# 2_FPGA.net
KiCad netlist of a schematic drawn in Altium Designer
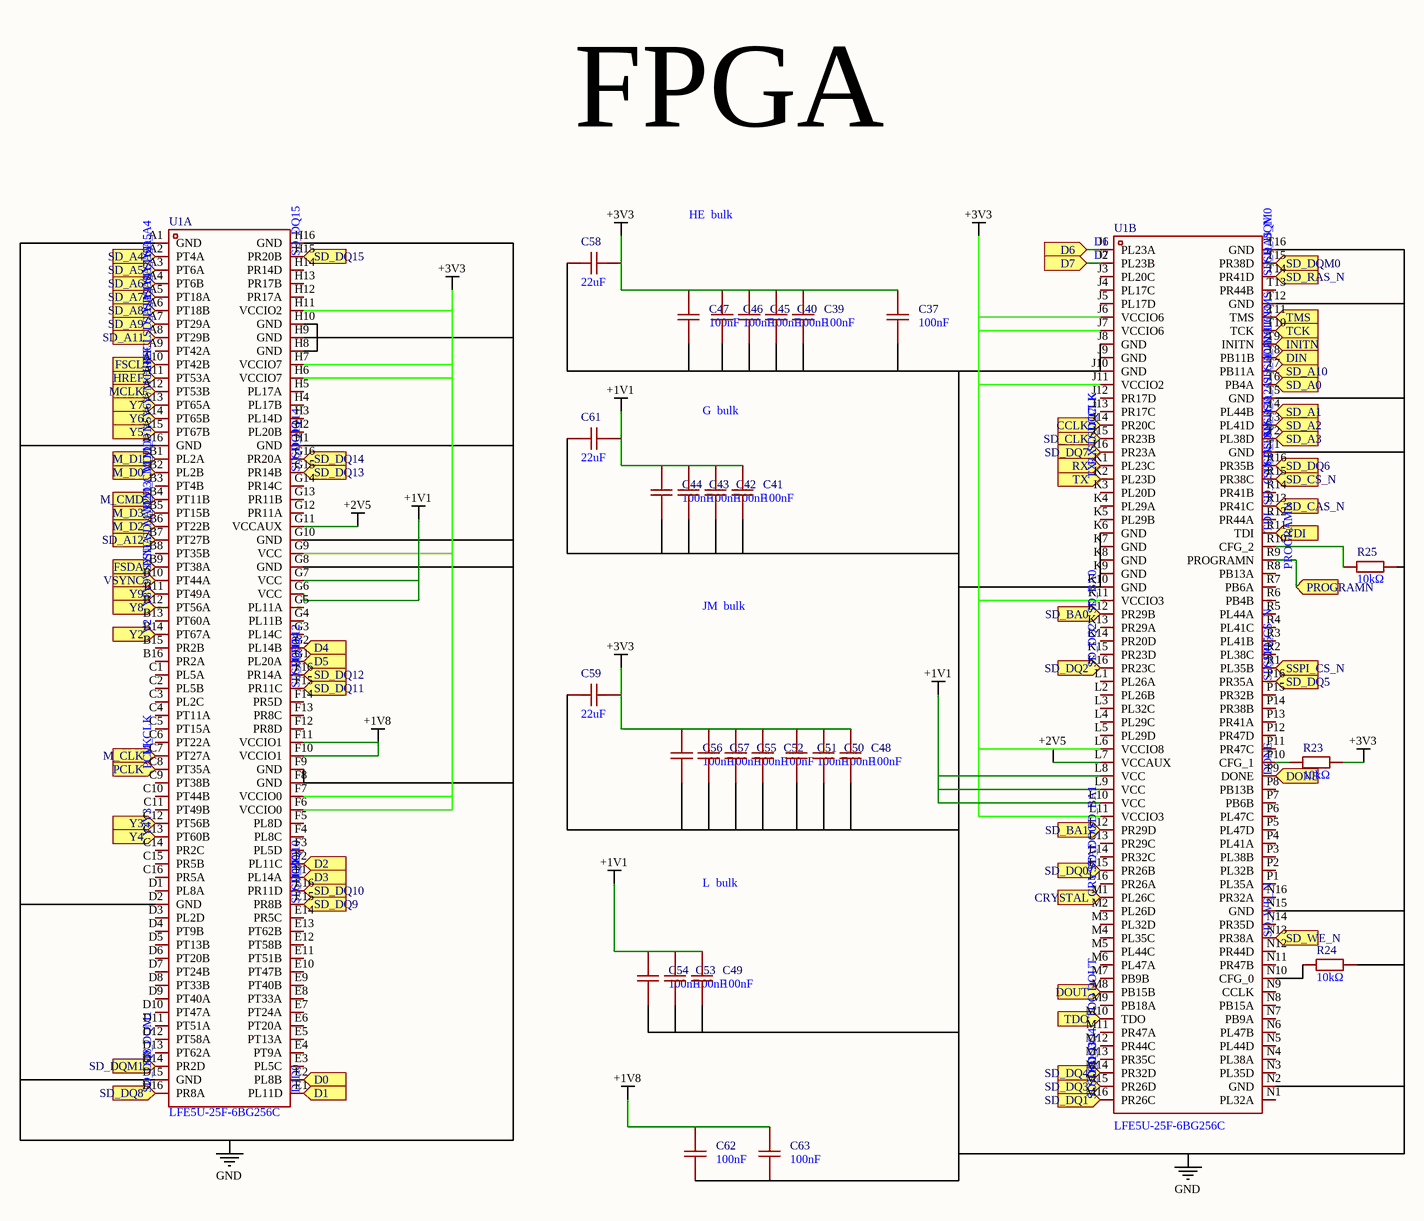
[diagram p0: 2_FPGA.schdoc]

(export (version "E")
  (design (tool "Eeschema 10.0.6"))
  (components
    (comp (ref "C37")
      (value "100nF")
      (footprint "C01005")
      (fields
        (field (name "MANUFACTURER") "muRata(村田)")
        (field (name "MANUFACTURER PART") "GRM022R60J104KE15D")
        (field (name "TOLERANCE") "±10%")
      )
      (libsource (lib "altium-import") (part "root_2_GRM022R60J104KE15D_"))
    )
    (comp (ref "C39")
      (value "100nF")
      (footprint "C01005")
      (fields
        (field (name "MANUFACTURER") "muRata(村田)")
        (field (name "MANUFACTURER PART") "GRM022R60J104KE15D")
        (field (name "TOLERANCE") "±10%")
      )
      (libsource (lib "altium-import") (part "root_2_GRM022R60J104KE15D_"))
    )
    (comp (ref "C40")
      (value "100nF")
      (footprint "C01005")
      (fields
        (field (name "MANUFACTURER") "muRata(村田)")
        (field (name "MANUFACTURER PART") "GRM022R60J104KE15D")
        (field (name "TOLERANCE") "±10%")
      )
      (libsource (lib "altium-import") (part "root_2_GRM022R60J104KE15D_"))
    )
    (comp (ref "C41")
      (value "100nF")
      (footprint "C01005")
      (fields
        (field (name "MANUFACTURER") "muRata(村田)")
        (field (name "MANUFACTURER PART") "GRM022R60J104KE15D")
        (field (name "TOLERANCE") "±10%")
      )
      (libsource (lib "altium-import") (part "root_2_GRM022R60J104KE15D_"))
    )
    (comp (ref "C42")
      (value "100nF")
      (footprint "C01005")
      (fields
        (field (name "MANUFACTURER") "muRata(村田)")
        (field (name "MANUFACTURER PART") "GRM022R60J104KE15D")
        (field (name "TOLERANCE") "±10%")
      )
      (libsource (lib "altium-import") (part "root_2_GRM022R60J104KE15D_"))
    )
    (comp (ref "C43")
      (value "100nF")
      (footprint "C01005")
      (fields
        (field (name "MANUFACTURER") "muRata(村田)")
        (field (name "MANUFACTURER PART") "GRM022R60J104KE15D")
        (field (name "TOLERANCE") "±10%")
      )
      (libsource (lib "altium-import") (part "root_2_GRM022R60J104KE15D_"))
    )
    (comp (ref "C44")
      (value "100nF")
      (footprint "C01005")
      (fields
        (field (name "MANUFACTURER") "muRata(村田)")
        (field (name "MANUFACTURER PART") "GRM022R60J104KE15D")
        (field (name "TOLERANCE") "±10%")
      )
      (libsource (lib "altium-import") (part "root_2_GRM022R60J104KE15D_"))
    )
    (comp (ref "C45")
      (value "100nF")
      (footprint "C01005")
      (fields
        (field (name "MANUFACTURER") "muRata(村田)")
        (field (name "MANUFACTURER PART") "GRM022R60J104KE15D")
        (field (name "TOLERANCE") "±10%")
      )
      (libsource (lib "altium-import") (part "root_2_GRM022R60J104KE15D_"))
    )
    (comp (ref "C46")
      (value "100nF")
      (footprint "C01005")
      (fields
        (field (name "MANUFACTURER") "muRata(村田)")
        (field (name "MANUFACTURER PART") "GRM022R60J104KE15D")
        (field (name "TOLERANCE") "±10%")
      )
      (libsource (lib "altium-import") (part "root_2_GRM022R60J104KE15D_"))
    )
    (comp (ref "C47")
      (value "100nF")
      (footprint "C01005")
      (fields
        (field (name "MANUFACTURER") "muRata(村田)")
        (field (name "MANUFACTURER PART") "GRM022R60J104KE15D")
        (field (name "TOLERANCE") "±10%")
      )
      (libsource (lib "altium-import") (part "root_2_GRM022R60J104KE15D_"))
    )
    (comp (ref "C48")
      (value "100nF")
      (footprint "C01005")
      (fields
        (field (name "MANUFACTURER") "muRata(村田)")
        (field (name "MANUFACTURER PART") "GRM022R60J104KE15D")
        (field (name "TOLERANCE") "±10%")
      )
      (libsource (lib "altium-import") (part "root_2_GRM022R60J104KE15D_"))
    )
    (comp (ref "C49")
      (value "100nF")
      (footprint "C01005")
      (fields
        (field (name "MANUFACTURER") "muRata(村田)")
        (field (name "MANUFACTURER PART") "GRM022R60J104KE15D")
        (field (name "TOLERANCE") "±10%")
      )
      (libsource (lib "altium-import") (part "root_2_GRM022R60J104KE15D_"))
    )
    (comp (ref "C50")
      (value "100nF")
      (footprint "C01005")
      (fields
        (field (name "MANUFACTURER") "muRata(村田)")
        (field (name "MANUFACTURER PART") "GRM022R60J104KE15D")
        (field (name "TOLERANCE") "±10%")
      )
      (libsource (lib "altium-import") (part "root_2_GRM022R60J104KE15D_"))
    )
    (comp (ref "C51")
      (value "100nF")
      (footprint "C01005")
      (fields
        (field (name "MANUFACTURER") "muRata(村田)")
        (field (name "MANUFACTURER PART") "GRM022R60J104KE15D")
        (field (name "TOLERANCE") "±10%")
      )
      (libsource (lib "altium-import") (part "root_2_GRM022R60J104KE15D_"))
    )
    (comp (ref "C52")
      (value "100nF")
      (footprint "C01005")
      (fields
        (field (name "MANUFACTURER") "muRata(村田)")
        (field (name "MANUFACTURER PART") "GRM022R60J104KE15D")
        (field (name "TOLERANCE") "±10%")
      )
      (libsource (lib "altium-import") (part "root_2_GRM022R60J104KE15D_"))
    )
    (comp (ref "C53")
      (value "100nF")
      (footprint "C01005")
      (fields
        (field (name "MANUFACTURER") "muRata(村田)")
        (field (name "MANUFACTURER PART") "GRM022R60J104KE15D")
        (field (name "TOLERANCE") "±10%")
      )
      (libsource (lib "altium-import") (part "root_2_GRM022R60J104KE15D_"))
    )
    (comp (ref "C54")
      (value "100nF")
      (footprint "C01005")
      (fields
        (field (name "MANUFACTURER") "muRata(村田)")
        (field (name "MANUFACTURER PART") "GRM022R60J104KE15D")
        (field (name "TOLERANCE") "±10%")
      )
      (libsource (lib "altium-import") (part "root_2_GRM022R60J104KE15D_"))
    )
    (comp (ref "C55")
      (value "100nF")
      (footprint "C01005")
      (fields
        (field (name "MANUFACTURER") "muRata(村田)")
        (field (name "MANUFACTURER PART") "GRM022R60J104KE15D")
        (field (name "TOLERANCE") "±10%")
      )
      (libsource (lib "altium-import") (part "root_2_GRM022R60J104KE15D_"))
    )
    (comp (ref "C56")
      (value "100nF")
      (footprint "C01005")
      (fields
        (field (name "MANUFACTURER") "muRata(村田)")
        (field (name "MANUFACTURER PART") "GRM022R60J104KE15D")
        (field (name "TOLERANCE") "±10%")
      )
      (libsource (lib "altium-import") (part "root_2_GRM022R60J104KE15D_"))
    )
    (comp (ref "C57")
      (value "100nF")
      (footprint "C01005")
      (fields
        (field (name "MANUFACTURER") "muRata(村田)")
        (field (name "MANUFACTURER PART") "GRM022R60J104KE15D")
        (field (name "TOLERANCE") "±10%")
      )
      (libsource (lib "altium-import") (part "root_2_GRM022R60J104KE15D_"))
    )
    (comp (ref "C58")
      (value "22uF")
      (footprint "C0603")
      (fields
        (field (name "MANUFACTURER") "CCTC(三环)")
        (field (name "MANUFACTURER PART") "TCC0603X5R226M6R3CT")
        (field (name "TOLERANCE") "±20%")
      )
      (libsource (lib "altium-import") (part "root_1_TCC0603X5R226M6R3CT_"))
    )
    (comp (ref "C59")
      (value "22uF")
      (footprint "C0603")
      (fields
        (field (name "MANUFACTURER") "CCTC(三环)")
        (field (name "MANUFACTURER PART") "TCC0603X5R226M6R3CT")
        (field (name "TOLERANCE") "±20%")
      )
      (libsource (lib "altium-import") (part "root_1_TCC0603X5R226M6R3CT_"))
    )
    (comp (ref "C61")
      (value "22uF")
      (footprint "C0603")
      (fields
        (field (name "MANUFACTURER") "CCTC(三环)")
        (field (name "MANUFACTURER PART") "TCC0603X5R226M6R3CT")
        (field (name "TOLERANCE") "±20%")
      )
      (libsource (lib "altium-import") (part "root_1_TCC0603X5R226M6R3CT_"))
    )
    (comp (ref "C62")
      (value "100nF")
      (footprint "C01005")
      (fields
        (field (name "MANUFACTURER") "muRata(村田)")
        (field (name "MANUFACTURER PART") "GRM022R60J104KE15D")
        (field (name "TOLERANCE") "±10%")
      )
      (libsource (lib "altium-import") (part "root_2_GRM022R60J104KE15D_"))
    )
    (comp (ref "C63")
      (value "100nF")
      (footprint "C01005")
      (fields
        (field (name "MANUFACTURER") "muRata(村田)")
        (field (name "MANUFACTURER PART") "GRM022R60J104KE15D")
        (field (name "TOLERANCE") "±10%")
      )
      (libsource (lib "altium-import") (part "root_2_GRM022R60J104KE15D_"))
    )
    (comp (ref "R23")
      (value "10kΩ")
      (footprint "R0402")
      (fields
        (field (name "MANUFACTURER") "UNI-ROYAL(厚声)")
        (field (name "MANUFACTURER PART") "0402WGF1002TCE")
        (field (name "TOLERANCE") "±1%")
      )
      (libsource (lib "altium-import") (part "root_2_0402WGF1002TCE_"))
    )
    (comp (ref "R24")
      (value "10kΩ")
      (footprint "R0402")
      (fields
        (field (name "MANUFACTURER") "UNI-ROYAL(厚声)")
        (field (name "MANUFACTURER PART") "0402WGF1002TCE")
        (field (name "TOLERANCE") "±1%")
      )
      (libsource (lib "altium-import") (part "root_2_0402WGF1002TCE_"))
    )
    (comp (ref "R25")
      (value "10kΩ")
      (footprint "R0402")
      (fields
        (field (name "MANUFACTURER") "UNI-ROYAL(厚声)")
        (field (name "MANUFACTURER PART") "0402WGF1002TCE")
        (field (name "TOLERANCE") "±1%")
      )
      (libsource (lib "altium-import") (part "root_2_0402WGF1002TCE_"))
    )
    (comp (ref "U1")
      (value "LFE5U-25F-6BG256C")
      (footprint "CABGA-256_L14.0-W14.0-R16-C16-P0.80-TL")
      (fields (field (name "MANUFACTURER") "LATTICE(莱迪思)"))
      (libsource (lib "altium-import") (part "root_0_LFE5U-25F-6BG256C_"))
    )
  )
  (nets
    (net (code "1") (name "+1V1") (class "Default")
      (node (ref "C41") (pin "1") (pinfunction "1_1") (pintype "passive"))
      (node (ref "C42") (pin "1") (pinfunction "1_1") (pintype "passive"))
      (node (ref "C43") (pin "1") (pinfunction "1_1") (pintype "passive"))
      (node (ref "C44") (pin "1") (pinfunction "1_1") (pintype "passive"))
      (node (ref "C49") (pin "1") (pinfunction "1_1") (pintype "passive"))
      (node (ref "C53") (pin "1") (pinfunction "1_1") (pintype "passive"))
      (node (ref "C54") (pin "1") (pinfunction "1_1") (pintype "passive"))
      (node (ref "C61") (pin "1") (pinfunction "1_1") (pintype "passive"))
      (node (ref "U1") (pin "G6") (pinfunction "VCC_G6") (pintype "passive"))
      (node (ref "U1") (pin "G7") (pinfunction "VCC_G7") (pintype "passive"))
      (node (ref "U1") (pin "L10") (pinfunction "VCC_L10") (pintype "passive"))
      (node (ref "U1") (pin "L8") (pinfunction "VCC_L8") (pintype "passive"))
      (node (ref "U1") (pin "L9") (pinfunction "VCC_L9") (pintype "passive"))
    )
    (net (code "2") (name "+1V8") (class "Default")
      (node (ref "C62") (pin "1") (pinfunction "1_1") (pintype "passive"))
      (node (ref "C63") (pin "1") (pinfunction "1_1") (pintype "passive"))
      (node (ref "U1") (pin "F10") (pinfunction "VCCIO1_F10") (pintype "passive"))
      (node (ref "U1") (pin "F11") (pinfunction "VCCIO1_F11") (pintype "passive"))
    )
    (net (code "3") (name "+2V5") (class "Default")
      (node (ref "U1") (pin "G11") (pinfunction "VCCAUX_G11") (pintype "passive"))
      (node (ref "U1") (pin "L7") (pinfunction "VCCAUX_L7") (pintype "passive"))
    )
    (net (code "4") (name "+3V3") (class "Default")
      (node (ref "C37") (pin "1") (pinfunction "1_1") (pintype "passive"))
      (node (ref "C39") (pin "1") (pinfunction "1_1") (pintype "passive"))
      (node (ref "C40") (pin "1") (pinfunction "1_1") (pintype "passive"))
      (node (ref "C45") (pin "1") (pinfunction "1_1") (pintype "passive"))
      (node (ref "C46") (pin "1") (pinfunction "1_1") (pintype "passive"))
      (node (ref "C47") (pin "1") (pinfunction "1_1") (pintype "passive"))
      (node (ref "C48") (pin "1") (pinfunction "1_1") (pintype "passive"))
      (node (ref "C50") (pin "1") (pinfunction "1_1") (pintype "passive"))
      (node (ref "C51") (pin "1") (pinfunction "1_1") (pintype "passive"))
      (node (ref "C52") (pin "1") (pinfunction "1_1") (pintype "passive"))
      (node (ref "C55") (pin "1") (pinfunction "1_1") (pintype "passive"))
      (node (ref "C56") (pin "1") (pinfunction "1_1") (pintype "passive"))
      (node (ref "C57") (pin "1") (pinfunction "1_1") (pintype "passive"))
      (node (ref "C58") (pin "1") (pinfunction "1_1") (pintype "passive"))
      (node (ref "C59") (pin "1") (pinfunction "1_1") (pintype "passive"))
      (node (ref "R23") (pin "1") (pinfunction "1_1") (pintype "passive"))
      (node (ref "U1") (pin "F6") (pinfunction "VCCIO0_F6") (pintype "passive"))
      (node (ref "U1") (pin "F7") (pinfunction "VCCIO0_F7") (pintype "passive"))
      (node (ref "U1") (pin "G9") (pinfunction "VCC_G9") (pintype "passive"))
      (node (ref "U1") (pin "H11") (pinfunction "VCCIO2_H11") (pintype "passive"))
      (node (ref "U1") (pin "H6") (pinfunction "VCCIO7_H6") (pintype "passive"))
      (node (ref "U1") (pin "H7") (pinfunction "VCCIO7_H7") (pintype "passive"))
      (node (ref "U1") (pin "J11") (pinfunction "VCCIO2_J11") (pintype "passive"))
      (node (ref "U1") (pin "J6") (pinfunction "VCCIO6_J6") (pintype "passive"))
      (node (ref "U1") (pin "J7") (pinfunction "VCCIO6_J7") (pintype "passive"))
      (node (ref "U1") (pin "K11") (pinfunction "VCCIO3_K11") (pintype "passive"))
      (node (ref "U1") (pin "L11") (pinfunction "VCCIO3_L11") (pintype "passive"))
      (node (ref "U1") (pin "L6") (pinfunction "VCCIO8_L6") (pintype "passive"))
    )
    (net (code "5") (name "/CCLK") (class "Default")
      (node (ref "U1") (pin "J14") (pinfunction "PR20C_J14") (pintype "passive"))
    )
    (net (code "6") (name "/CRYSTAL") (class "Default")
      (node (ref "U1") (pin "M1") (pinfunction "PL26C_M1") (pintype "passive"))
    )
    (net (code "7") (name "/D0") (class "Default")
      (node (ref "U1") (pin "E2") (pinfunction "PL8B_E2") (pintype "passive"))
    )
    (net (code "8") (name "/D1") (class "Default")
      (node (ref "U1") (pin "E1") (pinfunction "PL11D_E1") (pintype "passive"))
    )
    (net (code "9") (name "/D2") (class "Default")
      (node (ref "U1") (pin "F2") (pinfunction "PL11C_F2") (pintype "passive"))
    )
    (net (code "10") (name "/D3") (class "Default")
      (node (ref "U1") (pin "F1") (pinfunction "PL14A_F1") (pintype "passive"))
    )
    (net (code "11") (name "/D4") (class "Default")
      (node (ref "U1") (pin "G2") (pinfunction "PL14B_G2") (pintype "passive"))
    )
    (net (code "12") (name "/D5") (class "Default")
      (node (ref "U1") (pin "G1") (pinfunction "PL20A_G1") (pintype "passive"))
    )
    (net (code "13") (name "/D6") (class "Default")
      (node (ref "U1") (pin "J1") (pinfunction "PL23A_J1") (pintype "passive"))
    )
    (net (code "14") (name "/D7") (class "Default")
      (node (ref "U1") (pin "J2") (pinfunction "PL23B_J2") (pintype "passive"))
    )
    (net (code "15") (name "/DIN") (class "Default")
      (node (ref "U1") (pin "T8") (pinfunction "PB11B_T8") (pintype "passive"))
    )
    (net (code "16") (name "/DONE") (class "Default")
      (node (ref "U1") (pin "P9") (pinfunction "DONE_P9") (pintype "passive"))
    )
    (net (code "17") (name "/DOUT") (class "Default")
      (node (ref "U1") (pin "M8") (pinfunction "PB15B_M8") (pintype "passive"))
    )
    (net (code "18") (name "/FSCL") (class "Default")
      (node (ref "U1") (pin "A10") (pinfunction "PT42B_A10") (pintype "passive"))
    )
    (net (code "19") (name "/FSDA") (class "Default")
      (node (ref "U1") (pin "B9") (pinfunction "PT38A_B9") (pintype "passive"))
    )
    (net (code "20") (name "/HREF") (class "Default")
      (node (ref "U1") (pin "A11") (pinfunction "PT53A_A11") (pintype "passive"))
    )
    (net (code "21") (name "/INITN") (class "Default")
      (node (ref "U1") (pin "T9") (pinfunction "INITN_T9") (pintype "passive"))
    )
    (net (code "22") (name "/MCLK") (class "Default")
      (node (ref "U1") (pin "A12") (pinfunction "PT53B_A12") (pintype "passive"))
    )
    (net (code "23") (name "/M_CLK") (class "Default")
      (node (ref "U1") (pin "C7") (pinfunction "PT27A_C7") (pintype "passive"))
    )
    (net (code "24") (name "/M_CMD") (class "Default")
      (node (ref "U1") (pin "B4") (pinfunction "PT11B_B4") (pintype "passive"))
    )
    (net (code "25") (name "/M_D0") (class "Default")
      (node (ref "U1") (pin "B2") (pinfunction "PL2B_B2") (pintype "passive"))
    )
    (net (code "26") (name "/M_D1") (class "Default")
      (node (ref "U1") (pin "B1") (pinfunction "PL2A_B1") (pintype "passive"))
    )
    (net (code "27") (name "/M_D2") (class "Default")
      (node (ref "U1") (pin "B6") (pinfunction "PT22B_B6") (pintype "passive"))
    )
    (net (code "28") (name "/M_D3") (class "Default")
      (node (ref "U1") (pin "B5") (pinfunction "PT15B_B5") (pintype "passive"))
    )
    (net (code "29") (name "/PCLK") (class "Default")
      (node (ref "U1") (pin "C8") (pinfunction "PT35A_C8") (pintype "passive"))
    )
    (net (code "30") (name "/PROGRAMN") (class "Default")
      (node (ref "U1") (pin "R9") (pinfunction "PROGRAMN_R9") (pintype "passive"))
    )
    (net (code "31") (name "/RX") (class "Default")
      (node (ref "U1") (pin "K1") (pinfunction "PL23C_K1") (pintype "passive"))
    )
    (net (code "32") (name "/SD_A0") (class "Default")
      (node (ref "U1") (pin "T6") (pinfunction "PB4A_T6") (pintype "passive"))
    )
    (net (code "33") (name "/SD_A1") (class "Default")
      (node (ref "U1") (pin "T4") (pinfunction "PL44B_T4") (pintype "passive"))
    )
    (net (code "34") (name "/SD_A2") (class "Default")
      (node (ref "U1") (pin "T3") (pinfunction "PL41D_T3") (pintype "passive"))
    )
    (net (code "35") (name "/SD_A3") (class "Default")
      (node (ref "U1") (pin "T2") (pinfunction "PL38D_T2") (pintype "passive"))
    )
    (net (code "36") (name "/SD_A4") (class "Default")
      (node (ref "U1") (pin "A2") (pinfunction "PT4A_A2") (pintype "passive"))
    )
    (net (code "37") (name "/SD_A5") (class "Default")
      (node (ref "U1") (pin "A3") (pinfunction "PT6A_A3") (pintype "passive"))
    )
    (net (code "38") (name "/SD_A6") (class "Default")
      (node (ref "U1") (pin "A4") (pinfunction "PT6B_A4") (pintype "passive"))
    )
    (net (code "39") (name "/SD_A7") (class "Default")
      (node (ref "U1") (pin "A5") (pinfunction "PT18A_A5") (pintype "passive"))
    )
    (net (code "40") (name "/SD_A8") (class "Default")
      (node (ref "U1") (pin "A6") (pinfunction "PT18B_A6") (pintype "passive"))
    )
    (net (code "41") (name "/SD_A9") (class "Default")
      (node (ref "U1") (pin "A7") (pinfunction "PT29A_A7") (pintype "passive"))
    )
    (net (code "42") (name "/SD_A10") (class "Default")
      (node (ref "U1") (pin "T7") (pinfunction "PB11A_T7") (pintype "passive"))
    )
    (net (code "43") (name "/SD_A11") (class "Default")
      (node (ref "U1") (pin "A8") (pinfunction "PT29B_A8") (pintype "passive"))
    )
    (net (code "44") (name "/SD_A12") (class "Default")
      (node (ref "U1") (pin "B7") (pinfunction "PT27B_B7") (pintype "passive"))
    )
    (net (code "45") (name "/SD_BA0") (class "Default")
      (node (ref "U1") (pin "K12") (pinfunction "PR29B_K12") (pintype "passive"))
    )
    (net (code "46") (name "/SD_BA1") (class "Default")
      (node (ref "U1") (pin "L12") (pinfunction "PR29D_L12") (pintype "passive"))
    )
    (net (code "47") (name "/SD_CAS_N") (class "Default")
      (node (ref "U1") (pin "R13") (pinfunction "PR41C_R13") (pintype "passive"))
    )
    (net (code "48") (name "/SD_CLK") (class "Default")
      (node (ref "U1") (pin "J15") (pinfunction "PR23B_J15") (pintype "passive"))
    )
    (net (code "49") (name "/SD_CS_N") (class "Default")
      (node (ref "U1") (pin "R15") (pinfunction "PR38C_R15") (pintype "passive"))
    )
    (net (code "50") (name "/SD_DQ0") (class "Default")
      (node (ref "U1") (pin "L15") (pinfunction "PR26B_L15") (pintype "passive"))
    )
    (net (code "51") (name "/SD_DQ1") (class "Default")
      (node (ref "U1") (pin "M16") (pinfunction "PR26C_M16") (pintype "passive"))
    )
    (net (code "52") (name "/SD_DQ2") (class "Default")
      (node (ref "U1") (pin "K16") (pinfunction "PR23C_K16") (pintype "passive"))
    )
    (net (code "53") (name "/SD_DQ3") (class "Default")
      (node (ref "U1") (pin "M15") (pinfunction "PR26D_M15") (pintype "passive"))
    )
    (net (code "54") (name "/SD_DQ4") (class "Default")
      (node (ref "U1") (pin "M14") (pinfunction "PR32D_M14") (pintype "passive"))
    )
    (net (code "55") (name "/SD_DQ5") (class "Default")
      (node (ref "U1") (pin "P16") (pinfunction "PR35A_P16") (pintype "passive"))
    )
    (net (code "56") (name "/SD_DQ6") (class "Default")
      (node (ref "U1") (pin "R16") (pinfunction "PR35B_R16") (pintype "passive"))
    )
    (net (code "57") (name "/SD_DQ7") (class "Default")
      (node (ref "U1") (pin "J16") (pinfunction "PR23A_J16") (pintype "passive"))
    )
    (net (code "58") (name "/SD_DQ8") (class "Default")
      (node (ref "U1") (pin "D16") (pinfunction "PR8A_D16") (pintype "passive"))
    )
    (net (code "59") (name "/SD_DQ9") (class "Default")
      (node (ref "U1") (pin "E15") (pinfunction "PR8B_E15") (pintype "passive"))
    )
    (net (code "60") (name "/SD_DQ10") (class "Default")
      (node (ref "U1") (pin "E16") (pinfunction "PR11D_E16") (pintype "passive"))
    )
    (net (code "61") (name "/SD_DQ11") (class "Default")
      (node (ref "U1") (pin "F15") (pinfunction "PR11C_F15") (pintype "passive"))
    )
    (net (code "62") (name "/SD_DQ12") (class "Default")
      (node (ref "U1") (pin "F16") (pinfunction "PR14A_F16") (pintype "passive"))
    )
    (net (code "63") (name "/SD_DQ13") (class "Default")
      (node (ref "U1") (pin "G15") (pinfunction "PR14B_G15") (pintype "passive"))
    )
    (net (code "64") (name "/SD_DQ14") (class "Default")
      (node (ref "U1") (pin "G16") (pinfunction "PR20A_G16") (pintype "passive"))
    )
    (net (code "65") (name "/SD_DQ15") (class "Default")
      (node (ref "U1") (pin "H15") (pinfunction "PR20B_H15") (pintype "passive"))
    )
    (net (code "66") (name "/SD_DQM0") (class "Default")
      (node (ref "U1") (pin "T15") (pinfunction "PR38D_T15") (pintype "passive"))
    )
    (net (code "67") (name "/SD_DQM1") (class "Default")
      (node (ref "U1") (pin "D14") (pinfunction "PR2D_D14") (pintype "passive"))
    )
    (net (code "68") (name "/SD_RAS_N") (class "Default")
      (node (ref "U1") (pin "T14") (pinfunction "PR41D_T14") (pintype "passive"))
    )
    (net (code "69") (name "/SD_WE_N") (class "Default")
      (node (ref "U1") (pin "N13") (pinfunction "PR38A_N13") (pintype "passive"))
    )
    (net (code "70") (name "/SSPI_CS_N") (class "Default")
      (node (ref "U1") (pin "R1") (pinfunction "PL35B_R1") (pintype "passive"))
    )
    (net (code "71") (name "/TCK") (class "Default")
      (node (ref "U1") (pin "T10") (pinfunction "TCK_T10") (pintype "passive"))
    )
    (net (code "72") (name "/TDI") (class "Default")
      (node (ref "U1") (pin "R11") (pinfunction "TDI_R11") (pintype "passive"))
    )
    (net (code "73") (name "/TDO") (class "Default")
      (node (ref "U1") (pin "M10") (pinfunction "TDO_M10") (pintype "passive"))
    )
    (net (code "74") (name "/TMS") (class "Default")
      (node (ref "U1") (pin "T11") (pinfunction "TMS_T11") (pintype "passive"))
    )
    (net (code "75") (name "/TX") (class "Default")
      (node (ref "U1") (pin "K2") (pinfunction "PL23D_K2") (pintype "passive"))
    )
    (net (code "76") (name "/VSYNC") (class "Default")
      (node (ref "U1") (pin "B10") (pinfunction "PT44A_B10") (pintype "passive"))
    )
    (net (code "77") (name "/Y2") (class "Default")
      (node (ref "U1") (pin "B14") (pinfunction "PT67A_B14") (pintype "passive"))
    )
    (net (code "78") (name "/Y3") (class "Default")
      (node (ref "U1") (pin "C12") (pinfunction "PT56B_C12") (pintype "passive"))
    )
    (net (code "79") (name "/Y4") (class "Default")
      (node (ref "U1") (pin "C13") (pinfunction "PT60B_C13") (pintype "passive"))
    )
    (net (code "80") (name "/Y5") (class "Default")
      (node (ref "U1") (pin "A15") (pinfunction "PT67B_A15") (pintype "passive"))
    )
    (net (code "81") (name "/Y6") (class "Default")
      (node (ref "U1") (pin "A14") (pinfunction "PT65B_A14") (pintype "passive"))
    )
    (net (code "82") (name "/Y7") (class "Default")
      (node (ref "U1") (pin "A13") (pinfunction "PT65A_A13") (pintype "passive"))
    )
    (net (code "83") (name "/Y8") (class "Default")
      (node (ref "U1") (pin "B12") (pinfunction "PT56A_B12") (pintype "passive"))
    )
    (net (code "84") (name "/Y9") (class "Default")
      (node (ref "U1") (pin "B11") (pinfunction "PT49A_B11") (pintype "passive"))
    )
    (net (code "85") (name "GND") (class "Default")
      (node (ref "C37") (pin "2") (pinfunction "2_2") (pintype "passive"))
      (node (ref "C39") (pin "2") (pinfunction "2_2") (pintype "passive"))
      (node (ref "C40") (pin "2") (pinfunction "2_2") (pintype "passive"))
      (node (ref "C41") (pin "2") (pinfunction "2_2") (pintype "passive"))
      (node (ref "C42") (pin "2") (pinfunction "2_2") (pintype "passive"))
      (node (ref "C43") (pin "2") (pinfunction "2_2") (pintype "passive"))
      (node (ref "C44") (pin "2") (pinfunction "2_2") (pintype "passive"))
      (node (ref "C45") (pin "2") (pinfunction "2_2") (pintype "passive"))
      (node (ref "C46") (pin "2") (pinfunction "2_2") (pintype "passive"))
      (node (ref "C47") (pin "2") (pinfunction "2_2") (pintype "passive"))
      (node (ref "C48") (pin "2") (pinfunction "2_2") (pintype "passive"))
      (node (ref "C49") (pin "2") (pinfunction "2_2") (pintype "passive"))
      (node (ref "C50") (pin "2") (pinfunction "2_2") (pintype "passive"))
      (node (ref "C51") (pin "2") (pinfunction "2_2") (pintype "passive"))
      (node (ref "C52") (pin "2") (pinfunction "2_2") (pintype "passive"))
      (node (ref "C53") (pin "2") (pinfunction "2_2") (pintype "passive"))
      (node (ref "C54") (pin "2") (pinfunction "2_2") (pintype "passive"))
      (node (ref "C55") (pin "2") (pinfunction "2_2") (pintype "passive"))
      (node (ref "C56") (pin "2") (pinfunction "2_2") (pintype "passive"))
      (node (ref "C57") (pin "2") (pinfunction "2_2") (pintype "passive"))
      (node (ref "C58") (pin "2") (pinfunction "2_2") (pintype "passive"))
      (node (ref "C59") (pin "2") (pinfunction "2_2") (pintype "passive"))
      (node (ref "C61") (pin "2") (pinfunction "2_2") (pintype "passive"))
      (node (ref "C62") (pin "2") (pinfunction "2_2") (pintype "passive"))
      (node (ref "C63") (pin "2") (pinfunction "2_2") (pintype "passive"))
      (node (ref "R24") (pin "1") (pinfunction "1_1") (pintype "passive"))
      (node (ref "R25") (pin "1") (pinfunction "1_1") (pintype "passive"))
      (node (ref "U1") (pin "A1") (pinfunction "GND_A1") (pintype "passive"))
      (node (ref "U1") (pin "A16") (pinfunction "GND_A16") (pintype "passive"))
      (node (ref "U1") (pin "D15") (pinfunction "GND_D15") (pintype "passive"))
      (node (ref "U1") (pin "D2") (pinfunction "GND_D2") (pintype "passive"))
      (node (ref "U1") (pin "F8") (pinfunction "GND_F8") (pintype "passive"))
      (node (ref "U1") (pin "F9") (pinfunction "GND_F9") (pintype "passive"))
      (node (ref "U1") (pin "G10") (pinfunction "GND_G10") (pintype "passive"))
      (node (ref "U1") (pin "G8") (pinfunction "GND_G8") (pintype "passive"))
      (node (ref "U1") (pin "H1") (pinfunction "GND_H1") (pintype "passive"))
      (node (ref "U1") (pin "H10") (pinfunction "GND_H10") (pintype "passive"))
      (node (ref "U1") (pin "H16") (pinfunction "GND_H16") (pintype "passive"))
      (node (ref "U1") (pin "H8") (pinfunction "GND_H8") (pintype "passive"))
      (node (ref "U1") (pin "H9") (pinfunction "GND_H9") (pintype "passive"))
      (node (ref "U1") (pin "J10") (pinfunction "GND_J10") (pintype "passive"))
      (node (ref "U1") (pin "J8") (pinfunction "GND_J8") (pintype "passive"))
      (node (ref "U1") (pin "J9") (pinfunction "GND_J9") (pintype "passive"))
      (node (ref "U1") (pin "K10") (pinfunction "GND_K10") (pintype "passive"))
      (node (ref "U1") (pin "K6") (pinfunction "GND_K6") (pintype "passive"))
      (node (ref "U1") (pin "K7") (pinfunction "GND_K7") (pintype "passive"))
      (node (ref "U1") (pin "K8") (pinfunction "GND_K8") (pintype "passive"))
      (node (ref "U1") (pin "K9") (pinfunction "GND_K9") (pintype "passive"))
      (node (ref "U1") (pin "N15") (pinfunction "GND_N15") (pintype "passive"))
      (node (ref "U1") (pin "N2") (pinfunction "GND_N2") (pintype "passive"))
      (node (ref "U1") (pin "T1") (pinfunction "GND_T1") (pintype "passive"))
      (node (ref "U1") (pin "T12") (pinfunction "GND_T12") (pintype "passive"))
      (node (ref "U1") (pin "T16") (pinfunction "GND_T16") (pintype "passive"))
      (node (ref "U1") (pin "T5") (pinfunction "GND_T5") (pintype "passive"))
    )
    (net (code "86") (name "Net-(U1B-CFG_0)") (class "Default")
      (node (ref "R24") (pin "2") (pinfunction "2_2") (pintype "passive"))
      (node (ref "U1") (pin "N10") (pinfunction "CFG_0_N10") (pintype "passive"))
    )
    (net (code "87") (name "Net-(U1B-CFG_1)") (class "Default")
      (node (ref "R23") (pin "2") (pinfunction "2_2") (pintype "passive"))
      (node (ref "U1") (pin "P10") (pinfunction "CFG_1_P10") (pintype "passive"))
    )
    (net (code "88") (name "Net-(U1B-CFG_2)") (class "Default")
      (node (ref "R25") (pin "2") (pinfunction "2_2") (pintype "passive"))
      (node (ref "U1") (pin "R10") (pinfunction "CFG_2_R10") (pintype "passive"))
    )
    (net (code "89") (name "unconnected-(U1A-PL2C-PadC3)") (class "Default")
      (node (ref "U1") (pin "C3") (pinfunction "PL2C_C3") (pintype "passive"))
    )
    (net (code "90") (name "unconnected-(U1A-PL2D-PadD3)") (class "Default")
      (node (ref "U1") (pin "D3") (pinfunction "PL2D_D3") (pintype "passive"))
    )
    (net (code "91") (name "unconnected-(U1A-PL5A-PadC1)") (class "Default")
      (node (ref "U1") (pin "C1") (pinfunction "PL5A_C1") (pintype "passive"))
    )
    (net (code "92") (name "unconnected-(U1A-PL5B-PadC2)") (class "Default")
      (node (ref "U1") (pin "C2") (pinfunction "PL5B_C2") (pintype "passive"))
    )
    (net (code "93") (name "unconnected-(U1A-PL5C-PadE3)") (class "Default")
      (node (ref "U1") (pin "E3") (pinfunction "PL5C_E3") (pintype "passive"))
    )
    (net (code "94") (name "unconnected-(U1A-PL5D-PadF3)") (class "Default")
      (node (ref "U1") (pin "F3") (pinfunction "PL5D_F3") (pintype "passive"))
    )
    (net (code "95") (name "unconnected-(U1A-PL8A-PadD1)") (class "Default")
      (node (ref "U1") (pin "D1") (pinfunction "PL8A_D1") (pintype "passive"))
    )
    (net (code "96") (name "unconnected-(U1A-PL8C-PadF4)") (class "Default")
      (node (ref "U1") (pin "F4") (pinfunction "PL8C_F4") (pintype "passive"))
    )
    (net (code "97") (name "unconnected-(U1A-PL8D-PadF5)") (class "Default")
      (node (ref "U1") (pin "F5") (pinfunction "PL8D_F5") (pintype "passive"))
    )
    (net (code "98") (name "unconnected-(U1A-PL11A-PadG5)") (class "Default")
      (node (ref "U1") (pin "G5") (pinfunction "PL11A_G5") (pintype "passive"))
    )
    (net (code "99") (name "unconnected-(U1A-PL11B-PadG4)") (class "Default")
      (node (ref "U1") (pin "G4") (pinfunction "PL11B_G4") (pintype "passive"))
    )
    (net (code "100") (name "unconnected-(U1A-PL14C-PadG3)") (class "Default")
      (node (ref "U1") (pin "G3") (pinfunction "PL14C_G3") (pintype "passive"))
    )
    (net (code "101") (name "unconnected-(U1A-PL14D-PadH3)") (class "Default")
      (node (ref "U1") (pin "H3") (pinfunction "PL14D_H3") (pintype "passive"))
    )
    (net (code "102") (name "unconnected-(U1A-PL17A-PadH5)") (class "Default")
      (node (ref "U1") (pin "H5") (pinfunction "PL17A_H5") (pintype "passive"))
    )
    (net (code "103") (name "unconnected-(U1A-PL17B-PadH4)") (class "Default")
      (node (ref "U1") (pin "H4") (pinfunction "PL17B_H4") (pintype "passive"))
    )
    (net (code "104") (name "unconnected-(U1A-PL20B-PadH2)") (class "Default")
      (node (ref "U1") (pin "H2") (pinfunction "PL20B_H2") (pintype "passive"))
    )
    (net (code "105") (name "unconnected-(U1A-PR2A-PadB16)") (class "Default")
      (node (ref "U1") (pin "B16") (pinfunction "PR2A_B16") (pintype "passive"))
    )
    (net (code "106") (name "unconnected-(U1A-PR2B-PadB15)") (class "Default")
      (node (ref "U1") (pin "B15") (pinfunction "PR2B_B15") (pintype "passive"))
    )
    (net (code "107") (name "unconnected-(U1A-PR2C-PadC14)") (class "Default")
      (node (ref "U1") (pin "C14") (pinfunction "PR2C_C14") (pintype "passive"))
    )
    (net (code "108") (name "unconnected-(U1A-PR5A-PadC16)") (class "Default")
      (node (ref "U1") (pin "C16") (pinfunction "PR5A_C16") (pintype "passive"))
    )
    (net (code "109") (name "unconnected-(U1A-PR5B-PadC15)") (class "Default")
      (node (ref "U1") (pin "C15") (pinfunction "PR5B_C15") (pintype "passive"))
    )
    (net (code "110") (name "unconnected-(U1A-PR5C-PadE14)") (class "Default")
      (node (ref "U1") (pin "E14") (pinfunction "PR5C_E14") (pintype "passive"))
    )
    (net (code "111") (name "unconnected-(U1A-PR5D-PadF14)") (class "Default")
      (node (ref "U1") (pin "F14") (pinfunction "PR5D_F14") (pintype "passive"))
    )
    (net (code "112") (name "unconnected-(U1A-PR8C-PadF13)") (class "Default")
      (node (ref "U1") (pin "F13") (pinfunction "PR8C_F13") (pintype "passive"))
    )
    (net (code "113") (name "unconnected-(U1A-PR8D-PadF12)") (class "Default")
      (node (ref "U1") (pin "F12") (pinfunction "PR8D_F12") (pintype "passive"))
    )
    (net (code "114") (name "unconnected-(U1A-PR11A-PadG12)") (class "Default")
      (node (ref "U1") (pin "G12") (pinfunction "PR11A_G12") (pintype "passive"))
    )
    (net (code "115") (name "unconnected-(U1A-PR11B-PadG13)") (class "Default")
      (node (ref "U1") (pin "G13") (pinfunction "PR11B_G13") (pintype "passive"))
    )
    (net (code "116") (name "unconnected-(U1A-PR14C-PadG14)") (class "Default")
      (node (ref "U1") (pin "G14") (pinfunction "PR14C_G14") (pintype "passive"))
    )
    (net (code "117") (name "unconnected-(U1A-PR14D-PadH14)") (class "Default")
      (node (ref "U1") (pin "H14") (pinfunction "PR14D_H14") (pintype "passive"))
    )
    (net (code "118") (name "unconnected-(U1A-PR17A-PadH12)") (class "Default")
      (node (ref "U1") (pin "H12") (pinfunction "PR17A_H12") (pintype "passive"))
    )
    (net (code "119") (name "unconnected-(U1A-PR17B-PadH13)") (class "Default")
      (node (ref "U1") (pin "H13") (pinfunction "PR17B_H13") (pintype "passive"))
    )
    (net (code "120") (name "unconnected-(U1A-PT4B-PadB3)") (class "Default")
      (node (ref "U1") (pin "B3") (pinfunction "PT4B_B3") (pintype "passive"))
    )
    (net (code "121") (name "unconnected-(U1A-PT9A-PadE4)") (class "Default")
      (node (ref "U1") (pin "E4") (pinfunction "PT9A_E4") (pintype "passive"))
    )
    (net (code "122") (name "unconnected-(U1A-PT9B-PadD4)") (class "Default")
      (node (ref "U1") (pin "D4") (pinfunction "PT9B_D4") (pintype "passive"))
    )
    (net (code "123") (name "unconnected-(U1A-PT11A-PadC4)") (class "Default")
      (node (ref "U1") (pin "C4") (pinfunction "PT11A_C4") (pintype "passive"))
    )
    (net (code "124") (name "unconnected-(U1A-PT13A-PadE5)") (class "Default")
      (node (ref "U1") (pin "E5") (pinfunction "PT13A_E5") (pintype "passive"))
    )
    (net (code "125") (name "unconnected-(U1A-PT13B-PadD5)") (class "Default")
      (node (ref "U1") (pin "D5") (pinfunction "PT13B_D5") (pintype "passive"))
    )
    (net (code "126") (name "unconnected-(U1A-PT15A-PadC5)") (class "Default")
      (node (ref "U1") (pin "C5") (pinfunction "PT15A_C5") (pintype "passive"))
    )
    (net (code "127") (name "unconnected-(U1A-PT20A-PadE6)") (class "Default")
      (node (ref "U1") (pin "E6") (pinfunction "PT20A_E6") (pintype "passive"))
    )
    (net (code "128") (name "unconnected-(U1A-PT20B-PadD6)") (class "Default")
      (node (ref "U1") (pin "D6") (pinfunction "PT20B_D6") (pintype "passive"))
    )
    (net (code "129") (name "unconnected-(U1A-PT22A-PadC6)") (class "Default")
      (node (ref "U1") (pin "C6") (pinfunction "PT22A_C6") (pintype "passive"))
    )
    (net (code "130") (name "unconnected-(U1A-PT24A-PadE7)") (class "Default")
      (node (ref "U1") (pin "E7") (pinfunction "PT24A_E7") (pintype "passive"))
    )
    (net (code "131") (name "unconnected-(U1A-PT24B-PadD7)") (class "Default")
      (node (ref "U1") (pin "D7") (pinfunction "PT24B_D7") (pintype "passive"))
    )
    (net (code "132") (name "unconnected-(U1A-PT33A-PadE8)") (class "Default")
      (node (ref "U1") (pin "E8") (pinfunction "PT33A_E8") (pintype "passive"))
    )
    (net (code "133") (name "unconnected-(U1A-PT33B-PadD8)") (class "Default")
      (node (ref "U1") (pin "D8") (pinfunction "PT33B_D8") (pintype "passive"))
    )
    (net (code "134") (name "unconnected-(U1A-PT35B-PadB8)") (class "Default")
      (node (ref "U1") (pin "B8") (pinfunction "PT35B_B8") (pintype "passive"))
    )
    (net (code "135") (name "unconnected-(U1A-PT38B-PadC9)") (class "Default")
      (node (ref "U1") (pin "C9") (pinfunction "PT38B_C9") (pintype "passive"))
    )
    (net (code "136") (name "unconnected-(U1A-PT40A-PadD9)") (class "Default")
      (node (ref "U1") (pin "D9") (pinfunction "PT40A_D9") (pintype "passive"))
    )
    (net (code "137") (name "unconnected-(U1A-PT40B-PadE9)") (class "Default")
      (node (ref "U1") (pin "E9") (pinfunction "PT40B_E9") (pintype "passive"))
    )
    (net (code "138") (name "unconnected-(U1A-PT42A-PadA9)") (class "Default")
      (node (ref "U1") (pin "A9") (pinfunction "PT42A_A9") (pintype "passive"))
    )
    (net (code "139") (name "unconnected-(U1A-PT44B-PadC10)") (class "Default")
      (node (ref "U1") (pin "C10") (pinfunction "PT44B_C10") (pintype "passive"))
    )
    (net (code "140") (name "unconnected-(U1A-PT47A-PadD10)") (class "Default")
      (node (ref "U1") (pin "D10") (pinfunction "PT47A_D10") (pintype "passive"))
    )
    (net (code "141") (name "unconnected-(U1A-PT47B-PadE10)") (class "Default")
      (node (ref "U1") (pin "E10") (pinfunction "PT47B_E10") (pintype "passive"))
    )
    (net (code "142") (name "unconnected-(U1A-PT49B-PadC11)") (class "Default")
      (node (ref "U1") (pin "C11") (pinfunction "PT49B_C11") (pintype "passive"))
    )
    (net (code "143") (name "unconnected-(U1A-PT51A-PadD11)") (class "Default")
      (node (ref "U1") (pin "D11") (pinfunction "PT51A_D11") (pintype "passive"))
    )
    (net (code "144") (name "unconnected-(U1A-PT51B-PadE11)") (class "Default")
      (node (ref "U1") (pin "E11") (pinfunction "PT51B_E11") (pintype "passive"))
    )
    (net (code "145") (name "unconnected-(U1A-PT58A-PadD12)") (class "Default")
      (node (ref "U1") (pin "D12") (pinfunction "PT58A_D12") (pintype "passive"))
    )
    (net (code "146") (name "unconnected-(U1A-PT58B-PadE12)") (class "Default")
      (node (ref "U1") (pin "E12") (pinfunction "PT58B_E12") (pintype "passive"))
    )
    (net (code "147") (name "unconnected-(U1A-PT60A-PadB13)") (class "Default")
      (node (ref "U1") (pin "B13") (pinfunction "PT60A_B13") (pintype "passive"))
    )
    (net (code "148") (name "unconnected-(U1A-PT62A-PadD13)") (class "Default")
      (node (ref "U1") (pin "D13") (pinfunction "PT62A_D13") (pintype "passive"))
    )
    (net (code "149") (name "unconnected-(U1A-PT62B-PadE13)") (class "Default")
      (node (ref "U1") (pin "E13") (pinfunction "PT62B_E13") (pintype "passive"))
    )
    (net (code "150") (name "unconnected-(U1B-CCLK-PadN9)") (class "Default")
      (node (ref "U1") (pin "N9") (pinfunction "CCLK_N9") (pintype "passive"))
    )
    (net (code "151") (name "unconnected-(U1B-PB4B-PadR6)") (class "Default")
      (node (ref "U1") (pin "R6") (pinfunction "PB4B_R6") (pintype "passive"))
    )
    (net (code "152") (name "unconnected-(U1B-PB6A-PadR7)") (class "Default")
      (node (ref "U1") (pin "R7") (pinfunction "PB6A_R7") (pintype "passive"))
    )
    (net (code "153") (name "unconnected-(U1B-PB6B-PadP7)") (class "Default")
      (node (ref "U1") (pin "P7") (pinfunction "PB6B_P7") (pintype "passive"))
    )
    (net (code "154") (name "unconnected-(U1B-PB9A-PadN7)") (class "Default")
      (node (ref "U1") (pin "N7") (pinfunction "PB9A_N7") (pintype "passive"))
    )
    (net (code "155") (name "unconnected-(U1B-PB9B-PadM7)") (class "Default")
      (node (ref "U1") (pin "M7") (pinfunction "PB9B_M7") (pintype "passive"))
    )
    (net (code "156") (name "unconnected-(U1B-PB13A-PadR8)") (class "Default")
      (node (ref "U1") (pin "R8") (pinfunction "PB13A_R8") (pintype "passive"))
    )
    (net (code "157") (name "unconnected-(U1B-PB13B-PadP8)") (class "Default")
      (node (ref "U1") (pin "P8") (pinfunction "PB13B_P8") (pintype "passive"))
    )
    (net (code "158") (name "unconnected-(U1B-PB15A-PadN8)") (class "Default")
      (node (ref "U1") (pin "N8") (pinfunction "PB15A_N8") (pintype "passive"))
    )
    (net (code "159") (name "unconnected-(U1B-PB18A-PadM9)") (class "Default")
      (node (ref "U1") (pin "M9") (pinfunction "PB18A_M9") (pintype "passive"))
    )
    (net (code "160") (name "unconnected-(U1B-PL17C-PadJ4)") (class "Default")
      (node (ref "U1") (pin "J4") (pinfunction "PL17C_J4") (pintype "passive"))
    )
    (net (code "161") (name "unconnected-(U1B-PL17D-PadJ5)") (class "Default")
      (node (ref "U1") (pin "J5") (pinfunction "PL17D_J5") (pintype "passive"))
    )
    (net (code "162") (name "unconnected-(U1B-PL20C-PadJ3)") (class "Default")
      (node (ref "U1") (pin "J3") (pinfunction "PL20C_J3") (pintype "passive"))
    )
    (net (code "163") (name "unconnected-(U1B-PL20D-PadK3)") (class "Default")
      (node (ref "U1") (pin "K3") (pinfunction "PL20D_K3") (pintype "passive"))
    )
    (net (code "164") (name "unconnected-(U1B-PL26A-PadL1)") (class "Default")
      (node (ref "U1") (pin "L1") (pinfunction "PL26A_L1") (pintype "passive"))
    )
    (net (code "165") (name "unconnected-(U1B-PL26B-PadL2)") (class "Default")
      (node (ref "U1") (pin "L2") (pinfunction "PL26B_L2") (pintype "passive"))
    )
    (net (code "166") (name "unconnected-(U1B-PL26D-PadM2)") (class "Default")
      (node (ref "U1") (pin "M2") (pinfunction "PL26D_M2") (pintype "passive"))
    )
    (net (code "167") (name "unconnected-(U1B-PL29A-PadK4)") (class "Default")
      (node (ref "U1") (pin "K4") (pinfunction "PL29A_K4") (pintype "passive"))
    )
    (net (code "168") (name "unconnected-(U1B-PL29B-PadK5)") (class "Default")
      (node (ref "U1") (pin "K5") (pinfunction "PL29B_K5") (pintype "passive"))
    )
    (net (code "169") (name "unconnected-(U1B-PL29C-PadL4)") (class "Default")
      (node (ref "U1") (pin "L4") (pinfunction "PL29C_L4") (pintype "passive"))
    )
    (net (code "170") (name "unconnected-(U1B-PL29D-PadL5)") (class "Default")
      (node (ref "U1") (pin "L5") (pinfunction "PL29D_L5") (pintype "passive"))
    )
    (net (code "171") (name "unconnected-(U1B-PL32A-PadN1)") (class "Default")
      (node (ref "U1") (pin "N1") (pinfunction "PL32A_N1") (pintype "passive"))
    )
    (net (code "172") (name "unconnected-(U1B-PL32B-PadP2)") (class "Default")
      (node (ref "U1") (pin "P2") (pinfunction "PL32B_P2") (pintype "passive"))
    )
    (net (code "173") (name "unconnected-(U1B-PL32C-PadL3)") (class "Default")
      (node (ref "U1") (pin "L3") (pinfunction "PL32C_L3") (pintype "passive"))
    )
    (net (code "174") (name "unconnected-(U1B-PL32D-PadM3)") (class "Default")
      (node (ref "U1") (pin "M3") (pinfunction "PL32D_M3") (pintype "passive"))
    )
    (net (code "175") (name "unconnected-(U1B-PL35A-PadP1)") (class "Default")
      (node (ref "U1") (pin "P1") (pinfunction "PL35A_P1") (pintype "passive"))
    )
    (net (code "176") (name "unconnected-(U1B-PL35C-PadM4)") (class "Default")
      (node (ref "U1") (pin "M4") (pinfunction "PL35C_M4") (pintype "passive"))
    )
    (net (code "177") (name "unconnected-(U1B-PL35D-PadN3)") (class "Default")
      (node (ref "U1") (pin "N3") (pinfunction "PL35D_N3") (pintype "passive"))
    )
    (net (code "178") (name "unconnected-(U1B-PL38A-PadN4)") (class "Default")
      (node (ref "U1") (pin "N4") (pinfunction "PL38A_N4") (pintype "passive"))
    )
    (net (code "179") (name "unconnected-(U1B-PL38B-PadP3)") (class "Default")
      (node (ref "U1") (pin "P3") (pinfunction "PL38B_P3") (pintype "passive"))
    )
    (net (code "180") (name "unconnected-(U1B-PL38C-PadR2)") (class "Default")
      (node (ref "U1") (pin "R2") (pinfunction "PL38C_R2") (pintype "passive"))
    )
    (net (code "181") (name "unconnected-(U1B-PL41A-PadP4)") (class "Default")
      (node (ref "U1") (pin "P4") (pinfunction "PL41A_P4") (pintype "passive"))
    )
    (net (code "182") (name "unconnected-(U1B-PL41B-PadR3)") (class "Default")
      (node (ref "U1") (pin "R3") (pinfunction "PL41B_R3") (pintype "passive"))
    )
    (net (code "183") (name "unconnected-(U1B-PL41C-PadR4)") (class "Default")
      (node (ref "U1") (pin "R4") (pinfunction "PL41C_R4") (pintype "passive"))
    )
    (net (code "184") (name "unconnected-(U1B-PL44A-PadR5)") (class "Default")
      (node (ref "U1") (pin "R5") (pinfunction "PL44A_R5") (pintype "passive"))
    )
    (net (code "185") (name "unconnected-(U1B-PL44C-PadM5)") (class "Default")
      (node (ref "U1") (pin "M5") (pinfunction "PL44C_M5") (pintype "passive"))
    )
    (net (code "186") (name "unconnected-(U1B-PL44D-PadN5)") (class "Default")
      (node (ref "U1") (pin "N5") (pinfunction "PL44D_N5") (pintype "passive"))
    )
    (net (code "187") (name "unconnected-(U1B-PL47A-PadM6)") (class "Default")
      (node (ref "U1") (pin "M6") (pinfunction "PL47A_M6") (pintype "passive"))
    )
    (net (code "188") (name "unconnected-(U1B-PL47B-PadN6)") (class "Default")
      (node (ref "U1") (pin "N6") (pinfunction "PL47B_N6") (pintype "passive"))
    )
    (net (code "189") (name "unconnected-(U1B-PL47C-PadP6)") (class "Default")
      (node (ref "U1") (pin "P6") (pinfunction "PL47C_P6") (pintype "passive"))
    )
    (net (code "190") (name "unconnected-(U1B-PL47D-PadP5)") (class "Default")
      (node (ref "U1") (pin "P5") (pinfunction "PL47D_P5") (pintype "passive"))
    )
    (net (code "191") (name "unconnected-(U1B-PR17C-PadJ13)") (class "Default")
      (node (ref "U1") (pin "J13") (pinfunction "PR17C_J13") (pintype "passive"))
    )
    (net (code "192") (name "unconnected-(U1B-PR17D-PadJ12)") (class "Default")
      (node (ref "U1") (pin "J12") (pinfunction "PR17D_J12") (pintype "passive"))
    )
    (net (code "193") (name "unconnected-(U1B-PR20D-PadK14)") (class "Default")
      (node (ref "U1") (pin "K14") (pinfunction "PR20D_K14") (pintype "passive"))
    )
    (net (code "194") (name "unconnected-(U1B-PR23D-PadK15)") (class "Default")
      (node (ref "U1") (pin "K15") (pinfunction "PR23D_K15") (pintype "passive"))
    )
    (net (code "195") (name "unconnected-(U1B-PR26A-PadL16)") (class "Default")
      (node (ref "U1") (pin "L16") (pinfunction "PR26A_L16") (pintype "passive"))
    )
    (net (code "196") (name "unconnected-(U1B-PR29A-PadK13)") (class "Default")
      (node (ref "U1") (pin "K13") (pinfunction "PR29A_K13") (pintype "passive"))
    )
    (net (code "197") (name "unconnected-(U1B-PR29C-PadL13)") (class "Default")
      (node (ref "U1") (pin "L13") (pinfunction "PR29C_L13") (pintype "passive"))
    )
    (net (code "198") (name "unconnected-(U1B-PR32A-PadN16)") (class "Default")
      (node (ref "U1") (pin "N16") (pinfunction "PR32A_N16") (pintype "passive"))
    )
    (net (code "199") (name "unconnected-(U1B-PR32B-PadP15)") (class "Default")
      (node (ref "U1") (pin "P15") (pinfunction "PR32B_P15") (pintype "passive"))
    )
    (net (code "200") (name "unconnected-(U1B-PR32C-PadL14)") (class "Default")
      (node (ref "U1") (pin "L14") (pinfunction "PR32C_L14") (pintype "passive"))
    )
    (net (code "201") (name "unconnected-(U1B-PR35C-PadM13)") (class "Default")
      (node (ref "U1") (pin "M13") (pinfunction "PR35C_M13") (pintype "passive"))
    )
    (net (code "202") (name "unconnected-(U1B-PR35D-PadN14)") (class "Default")
      (node (ref "U1") (pin "N14") (pinfunction "PR35D_N14") (pintype "passive"))
    )
    (net (code "203") (name "unconnected-(U1B-PR38B-PadP14)") (class "Default")
      (node (ref "U1") (pin "P14") (pinfunction "PR38B_P14") (pintype "passive"))
    )
    (net (code "204") (name "unconnected-(U1B-PR41A-PadP13)") (class "Default")
      (node (ref "U1") (pin "P13") (pinfunction "PR41A_P13") (pintype "passive"))
    )
    (net (code "205") (name "unconnected-(U1B-PR41B-PadR14)") (class "Default")
      (node (ref "U1") (pin "R14") (pinfunction "PR41B_R14") (pintype "passive"))
    )
    (net (code "206") (name "unconnected-(U1B-PR44A-PadR12)") (class "Default")
      (node (ref "U1") (pin "R12") (pinfunction "PR44A_R12") (pintype "passive"))
    )
    (net (code "207") (name "unconnected-(U1B-PR44B-PadT13)") (class "Default")
      (node (ref "U1") (pin "T13") (pinfunction "PR44B_T13") (pintype "passive"))
    )
    (net (code "208") (name "unconnected-(U1B-PR44C-PadM12)") (class "Default")
      (node (ref "U1") (pin "M12") (pinfunction "PR44C_M12") (pintype "passive"))
    )
    (net (code "209") (name "unconnected-(U1B-PR44D-PadN12)") (class "Default")
      (node (ref "U1") (pin "N12") (pinfunction "PR44D_N12") (pintype "passive"))
    )
    (net (code "210") (name "unconnected-(U1B-PR47A-PadM11)") (class "Default")
      (node (ref "U1") (pin "M11") (pinfunction "PR47A_M11") (pintype "passive"))
    )
    (net (code "211") (name "unconnected-(U1B-PR47B-PadN11)") (class "Default")
      (node (ref "U1") (pin "N11") (pinfunction "PR47B_N11") (pintype "passive"))
    )
    (net (code "212") (name "unconnected-(U1B-PR47C-PadP11)") (class "Default")
      (node (ref "U1") (pin "P11") (pinfunction "PR47C_P11") (pintype "passive"))
    )
    (net (code "213") (name "unconnected-(U1B-PR47D-PadP12)") (class "Default")
      (node (ref "U1") (pin "P12") (pinfunction "PR47D_P12") (pintype "passive"))
    )
  )
)
